# CPU_board.net
KiCad netlist of a schematic drawn in EAGLE
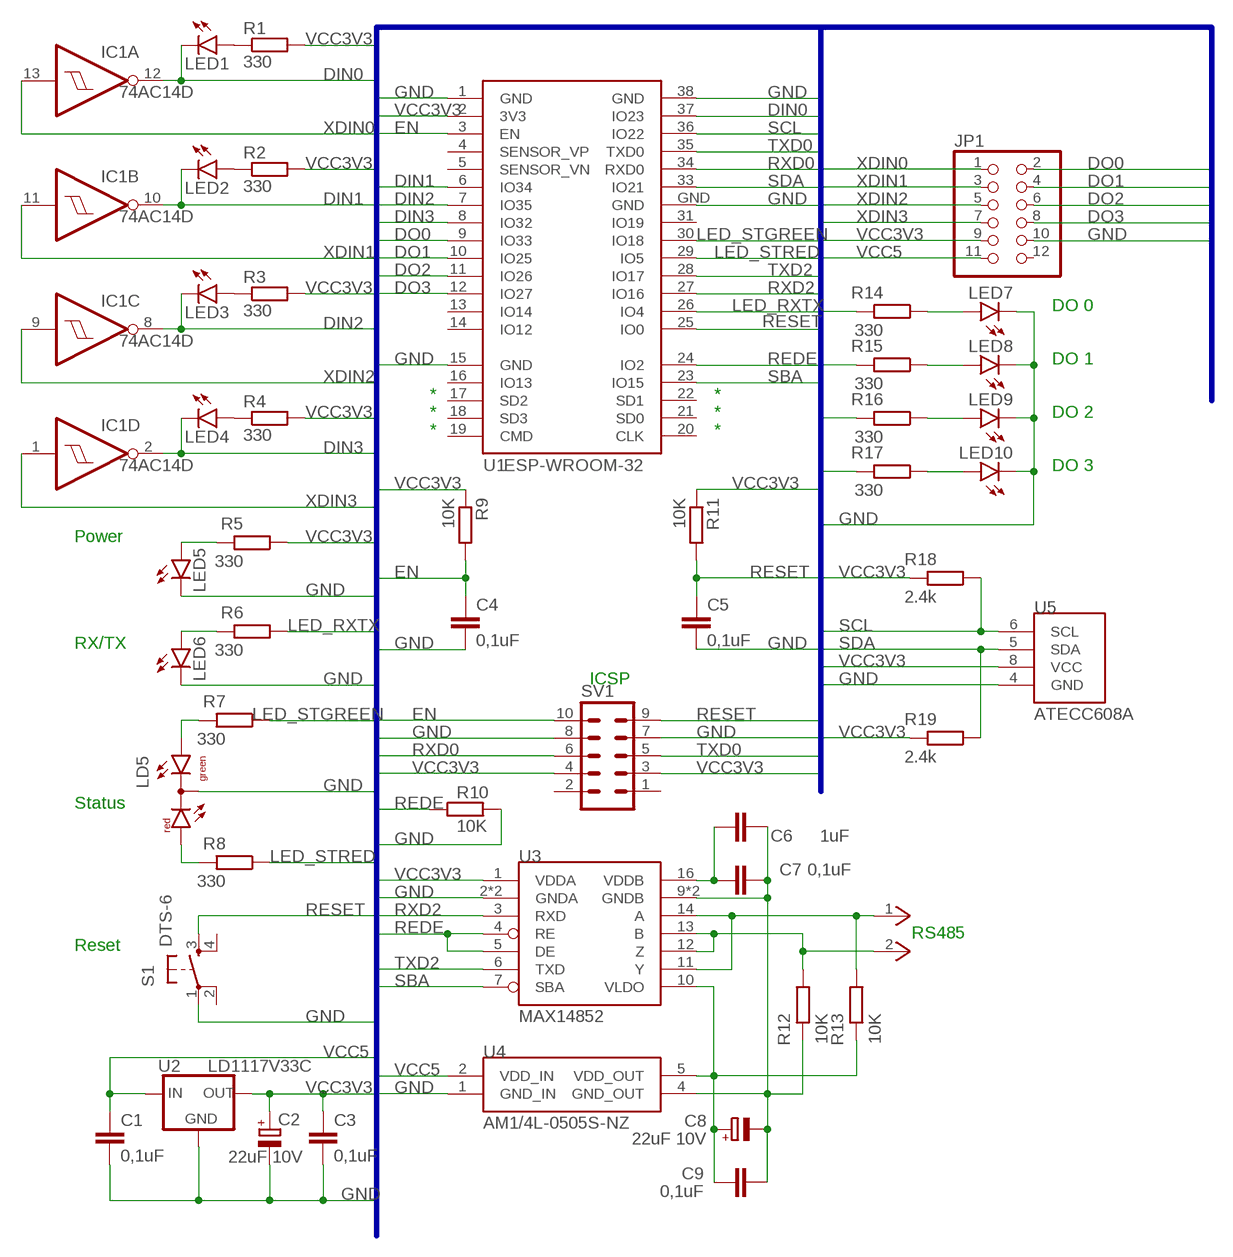
[diagram p0: schematic, sheet 1]

(export (version "E")
  (design (tool "Eeschema 10.0.6"))
  (components
    (comp (ref "C1")
      (value "0,1uF")
      (footprint "eagle-import:C0603")
      (libsource (lib "eagle-import") (part "C-EUC0603"))
    )
    (comp (ref "C2")
      (value "22uF 10V")
      (footprint "eagle-import:PANASONIC_A")
      (libsource (lib "eagle-import") (part "CPOL-EUA"))
    )
    (comp (ref "C3")
      (value "0,1uF")
      (footprint "eagle-import:C0603")
      (libsource (lib "eagle-import") (part "C-EUC0603"))
    )
    (comp (ref "C4")
      (value "0,1uF")
      (footprint "eagle-import:C0603")
      (libsource (lib "eagle-import") (part "C-EUC0603"))
    )
    (comp (ref "C5")
      (value "0,1uF")
      (footprint "eagle-import:C0603")
      (libsource (lib "eagle-import") (part "C-EUC0603"))
    )
    (comp (ref "C6")
      (value "1uF")
      (footprint "eagle-import:C0603")
      (libsource (lib "eagle-import") (part "C-EUC0603"))
    )
    (comp (ref "C7")
      (value "0,1uF")
      (footprint "eagle-import:C0603")
      (libsource (lib "eagle-import") (part "C-EUC0603"))
    )
    (comp (ref "C8")
      (value "22uF 10V")
      (footprint "eagle-import:PANASONIC_D")
      (libsource (lib "eagle-import") (part "CPOL-EUD"))
    )
    (comp (ref "C9")
      (value "0,1uF")
      (footprint "eagle-import:C0603")
      (libsource (lib "eagle-import") (part "C-EUC0603"))
    )
    (comp (ref "IC1")
      (value "74AC14D")
      (footprint "eagle-import:SO14")
      (libsource (lib "eagle-import") (part "7414DAC"))
    )
    (comp (ref "JP1")
      (value "PINHD-2X6")
      (footprint "eagle-import:2X06")
      (libsource (lib "eagle-import") (part "PINHD-2X6"))
    )
    (comp (ref "LD5")
      (value "DUOLED-RG-C")
      (footprint "eagle-import:DUOLED-C-5MM")
      (libsource (lib "eagle-import") (part "DUOLED-RG-C"))
    )
    (comp (ref "LED1")
      (value "LED5MM")
      (footprint "eagle-import:LED5MM")
      (libsource (lib "eagle-import") (part "LED5MM"))
    )
    (comp (ref "LED2")
      (value "LED5MM")
      (footprint "eagle-import:LED5MM")
      (libsource (lib "eagle-import") (part "LED5MM"))
    )
    (comp (ref "LED3")
      (value "LED5MM")
      (footprint "eagle-import:LED5MM")
      (libsource (lib "eagle-import") (part "LED5MM"))
    )
    (comp (ref "LED4")
      (value "LED5MM")
      (footprint "eagle-import:LED5MM")
      (libsource (lib "eagle-import") (part "LED5MM"))
    )
    (comp (ref "LED5")
      (value "LED5MM")
      (footprint "eagle-import:LED5MM")
      (libsource (lib "eagle-import") (part "LED5MM"))
    )
    (comp (ref "LED6")
      (value "LED5MM")
      (footprint "eagle-import:LED5MM")
      (libsource (lib "eagle-import") (part "LED5MM"))
    )
    (comp (ref "LED7")
      (value "LED5MM")
      (footprint "eagle-import:LED5MM")
      (libsource (lib "eagle-import") (part "LED5MM"))
    )
    (comp (ref "LED8")
      (value "LED5MM")
      (footprint "eagle-import:LED5MM")
      (libsource (lib "eagle-import") (part "LED5MM"))
    )
    (comp (ref "LED9")
      (value "LED5MM")
      (footprint "eagle-import:LED5MM")
      (libsource (lib "eagle-import") (part "LED5MM"))
    )
    (comp (ref "LED10")
      (value "LED5MM")
      (footprint "eagle-import:LED5MM")
      (libsource (lib "eagle-import") (part "LED5MM"))
    )
    (comp (ref "R1")
      (value "330")
      (footprint "eagle-import:R0603")
      (libsource (lib "eagle-import") (part "R-EU_R0603"))
    )
    (comp (ref "R2")
      (value "330")
      (footprint "eagle-import:R0603")
      (libsource (lib "eagle-import") (part "R-EU_R0603"))
    )
    (comp (ref "R3")
      (value "330")
      (footprint "eagle-import:R0603")
      (libsource (lib "eagle-import") (part "R-EU_R0603"))
    )
    (comp (ref "R4")
      (value "330")
      (footprint "eagle-import:R0603")
      (libsource (lib "eagle-import") (part "R-EU_R0603"))
    )
    (comp (ref "R5")
      (value "330")
      (footprint "eagle-import:R0603")
      (libsource (lib "eagle-import") (part "R-EU_R0603"))
    )
    (comp (ref "R6")
      (value "330")
      (footprint "eagle-import:R0603")
      (libsource (lib "eagle-import") (part "R-EU_R0603"))
    )
    (comp (ref "R7")
      (value "330")
      (footprint "eagle-import:R0603")
      (libsource (lib "eagle-import") (part "R-EU_R0603"))
    )
    (comp (ref "R8")
      (value "330")
      (footprint "eagle-import:R0603")
      (libsource (lib "eagle-import") (part "R-EU_R0603"))
    )
    (comp (ref "R9")
      (value "10K")
      (footprint "eagle-import:R0603")
      (libsource (lib "eagle-import") (part "R-EU_R0603"))
    )
    (comp (ref "R10")
      (value "10K")
      (footprint "eagle-import:R0603")
      (libsource (lib "eagle-import") (part "R-EU_R0603"))
    )
    (comp (ref "R11")
      (value "10K")
      (footprint "eagle-import:R0603")
      (libsource (lib "eagle-import") (part "R-EU_R0603"))
    )
    (comp (ref "R12")
      (value "10K")
      (footprint "eagle-import:R0603")
      (libsource (lib "eagle-import") (part "R-EU_R0603"))
    )
    (comp (ref "R13")
      (value "10K")
      (footprint "eagle-import:R0603")
      (libsource (lib "eagle-import") (part "R-EU_R0603"))
    )
    (comp (ref "R14")
      (value "330")
      (footprint "eagle-import:R0603")
      (libsource (lib "eagle-import") (part "R-EU_R0603"))
    )
    (comp (ref "R15")
      (value "330")
      (footprint "eagle-import:R0603")
      (libsource (lib "eagle-import") (part "R-EU_R0603"))
    )
    (comp (ref "R16")
      (value "330")
      (footprint "eagle-import:R0603")
      (libsource (lib "eagle-import") (part "R-EU_R0603"))
    )
    (comp (ref "R17")
      (value "330")
      (footprint "eagle-import:R0603")
      (libsource (lib "eagle-import") (part "R-EU_R0603"))
    )
    (comp (ref "R18")
      (value "2.4k")
      (footprint "eagle-import:R0603")
      (libsource (lib "eagle-import") (part "R-EU_R0603"))
    )
    (comp (ref "R19")
      (value "2.4k")
      (footprint "eagle-import:R0603")
      (libsource (lib "eagle-import") (part "R-EU_R0603"))
    )
    (comp (ref "S1")
      (value "DTS-6")
      (footprint "eagle-import:DTS-6")
      (libsource (lib "eagle-import") (part "DTS-6"))
    )
    (comp (ref "SV1")
      (value "ML10")
      (footprint "eagle-import:ML10")
      (libsource (lib "eagle-import") (part "ML10"))
    )
    (comp (ref "U1")
      (value "ESP-WROOM-32")
      (footprint "eagle-import:ESP-WROOM-32")
      (libsource (lib "eagle-import") (part "ESP-WROOM-32"))
    )
    (comp (ref "U2")
      (value "LD1117V33C")
      (footprint "eagle-import:SOT223")
      (libsource (lib "eagle-import") (part "LD1117V33C"))
    )
    (comp (ref "U3")
      (value "MAX14852")
      (footprint "eagle-import:SO16")
      (libsource (lib "eagle-import") (part "MAX14852"))
    )
    (comp (ref "U4")
      (value "AM1/4L-0505S-NZ")
      (footprint "eagle-import:AM1_4L")
      (libsource (lib "eagle-import") (part "AM1/4L"))
    )
    (comp (ref "U5")
      (value "ATECC608A")
      (footprint "eagle-import:SOIC8")
      (libsource (lib "eagle-import") (part "ATECC608A"))
    )
    (comp (ref "X1")
      (value "2EHDCR-5.08-02P")
      (footprint "eagle-import:2EHDCR-5.08-02P")
      (libsource (lib "eagle-import") (part "2EHDCR-5.08-02P"))
    )
  )
  (nets
    (net (code "1") (name "/DIN0") (class "Default")
      (node (ref "IC1") (pin "12") (pinfunction "O_12") (pintype "output"))
      (node (ref "LED1") (pin "K") (pinfunction "C_K") (pintype "passive"))
      (node (ref "U1") (pin "37") (pinfunction "IO23_37") (pintype "bidirectional"))
    )
    (net (code "2") (name "/DIN1") (class "Default")
      (node (ref "IC1") (pin "10") (pinfunction "O_10") (pintype "output"))
      (node (ref "LED2") (pin "K") (pinfunction "C_K") (pintype "passive"))
      (node (ref "U1") (pin "6") (pinfunction "IO34_6") (pintype "bidirectional"))
    )
    (net (code "3") (name "/DIN2") (class "Default")
      (node (ref "IC1") (pin "8") (pinfunction "O_8") (pintype "output"))
      (node (ref "LED3") (pin "K") (pinfunction "C_K") (pintype "passive"))
      (node (ref "U1") (pin "7") (pinfunction "IO35_7") (pintype "bidirectional"))
    )
    (net (code "4") (name "/DIN3") (class "Default")
      (node (ref "IC1") (pin "2") (pinfunction "O_2") (pintype "output"))
      (node (ref "LED4") (pin "K") (pinfunction "C_K") (pintype "passive"))
      (node (ref "U1") (pin "8") (pinfunction "IO32_8") (pintype "bidirectional"))
    )
    (net (code "5") (name "/DO0") (class "Default")
      (node (ref "JP1") (pin "2") (pinfunction "2_2") (pintype "passive"))
      (node (ref "R14") (pin "2") (pinfunction "2_2") (pintype "passive"))
      (node (ref "U1") (pin "9") (pinfunction "IO33_9") (pintype "bidirectional"))
    )
    (net (code "6") (name "/DO1") (class "Default")
      (node (ref "JP1") (pin "4") (pinfunction "4_4") (pintype "passive"))
      (node (ref "R15") (pin "2") (pinfunction "2_2") (pintype "passive"))
      (node (ref "U1") (pin "10") (pinfunction "IO25_10") (pintype "bidirectional"))
    )
    (net (code "7") (name "/DO2") (class "Default")
      (node (ref "JP1") (pin "6") (pinfunction "6_6") (pintype "passive"))
      (node (ref "R16") (pin "2") (pinfunction "2_2") (pintype "passive"))
      (node (ref "U1") (pin "11") (pinfunction "IO26_11") (pintype "bidirectional"))
    )
    (net (code "8") (name "/DO3") (class "Default")
      (node (ref "JP1") (pin "8") (pinfunction "8_8") (pintype "passive"))
      (node (ref "R17") (pin "2") (pinfunction "2_2") (pintype "passive"))
      (node (ref "U1") (pin "12") (pinfunction "IO27_12") (pintype "bidirectional"))
    )
    (net (code "9") (name "/EN") (class "Default")
      (node (ref "C4") (pin "1") (pinfunction "1_1") (pintype "passive"))
      (node (ref "R9") (pin "2") (pinfunction "2_2") (pintype "passive"))
      (node (ref "SV1") (pin "10") (pinfunction "10_10") (pintype "passive"))
      (node (ref "U1") (pin "3") (pinfunction "EN_3") (pintype "input"))
    )
    (net (code "10") (name "/GND") (class "Default")
      (node (ref "C1") (pin "2") (pinfunction "2_2") (pintype "passive"))
      (node (ref "C2") (pin "-") (pinfunction "-_-") (pintype "passive"))
      (node (ref "C3") (pin "2") (pinfunction "2_2") (pintype "passive"))
      (node (ref "C4") (pin "2") (pinfunction "2_2") (pintype "passive"))
      (node (ref "C5") (pin "2") (pinfunction "2_2") (pintype "passive"))
      (node (ref "JP1") (pin "10") (pinfunction "10_10") (pintype "passive"))
      (node (ref "LD5") (pin "C") (pinfunction "C_C") (pintype "passive"))
      (node (ref "LED10") (pin "K") (pinfunction "C_K") (pintype "passive"))
      (node (ref "LED5") (pin "K") (pinfunction "C_K") (pintype "passive"))
      (node (ref "LED6") (pin "K") (pinfunction "C_K") (pintype "passive"))
      (node (ref "LED7") (pin "K") (pinfunction "C_K") (pintype "passive"))
      (node (ref "LED8") (pin "K") (pinfunction "C_K") (pintype "passive"))
      (node (ref "LED9") (pin "K") (pinfunction "C_K") (pintype "passive"))
      (node (ref "R10") (pin "2") (pinfunction "2_2") (pintype "passive"))
      (node (ref "S1") (pin "1") (pinfunction "1_1") (pintype "passive"))
      (node (ref "SV1") (pin "7") (pinfunction "7_7") (pintype "passive"))
      (node (ref "SV1") (pin "8") (pinfunction "8_8") (pintype "passive"))
      (node (ref "U1") (pin "1") (pinfunction "GND_1") (pintype "power_in"))
      (node (ref "U1") (pin "15") (pinfunction "GND_15") (pintype "power_in"))
      (node (ref "U1") (pin "38") (pinfunction "GND_38") (pintype "power_in"))
      (node (ref "U1") (pin "GND") (pinfunction "GND_GND") (pintype "power_in"))
      (node (ref "U2") (pin "1") (pinfunction "GND_1") (pintype "input"))
      (node (ref "U3") (pin "2") (pinfunction "GNDA_2") (pintype "bidirectional"))
      (node (ref "U3") (pin "8") (pinfunction "GNDA_8") (pintype "bidirectional"))
      (node (ref "U4") (pin "1") (pinfunction "GND_IN_1") (pintype "bidirectional"))
      (node (ref "U5") (pin "4") (pinfunction "GND_4") (pintype "bidirectional"))
    )
    (net (code "11") (name "/LED_RXTX") (class "Default")
      (node (ref "R6") (pin "1") (pinfunction "1_1") (pintype "passive"))
      (node (ref "U1") (pin "26") (pinfunction "IO4_26") (pintype "bidirectional"))
    )
    (net (code "12") (name "/LED_STGREEN") (class "Default")
      (node (ref "R7") (pin "1") (pinfunction "1_1") (pintype "passive"))
      (node (ref "U1") (pin "30") (pinfunction "IO18_30") (pintype "bidirectional"))
    )
    (net (code "13") (name "/LED_STRED") (class "Default")
      (node (ref "R8") (pin "1") (pinfunction "1_1") (pintype "passive"))
      (node (ref "U1") (pin "29") (pinfunction "IO5_29") (pintype "bidirectional"))
    )
    (net (code "14") (name "/REDE") (class "Default")
      (node (ref "R10") (pin "1") (pinfunction "1_1") (pintype "passive"))
      (node (ref "U1") (pin "24") (pinfunction "IO2_24") (pintype "bidirectional"))
      (node (ref "U3") (pin "4") (pinfunction "RE_4") (pintype "bidirectional"))
      (node (ref "U3") (pin "5") (pinfunction "DE_5") (pintype "bidirectional"))
    )
    (net (code "15") (name "/RESET") (class "Default")
      (node (ref "C5") (pin "1") (pinfunction "1_1") (pintype "passive"))
      (node (ref "R11") (pin "2") (pinfunction "2_2") (pintype "passive"))
      (node (ref "S1") (pin "3") (pinfunction "3_3") (pintype "passive"))
      (node (ref "SV1") (pin "9") (pinfunction "9_9") (pintype "passive"))
      (node (ref "U1") (pin "25") (pinfunction "IO0_25") (pintype "bidirectional"))
    )
    (net (code "16") (name "/RXD0") (class "Default")
      (node (ref "SV1") (pin "6") (pinfunction "6_6") (pintype "passive"))
      (node (ref "U1") (pin "34") (pinfunction "RXD0_34") (pintype "bidirectional"))
    )
    (net (code "17") (name "/RXD2") (class "Default")
      (node (ref "U1") (pin "27") (pinfunction "IO16_27") (pintype "bidirectional"))
      (node (ref "U3") (pin "3") (pinfunction "RXD_3") (pintype "bidirectional"))
    )
    (net (code "18") (name "/SBA") (class "Default")
      (node (ref "U1") (pin "23") (pinfunction "IO15_23") (pintype "bidirectional"))
      (node (ref "U3") (pin "7") (pinfunction "SBA_7") (pintype "bidirectional"))
    )
    (net (code "19") (name "/SCL") (class "Default")
      (node (ref "R18") (pin "1") (pinfunction "1_1") (pintype "passive"))
      (node (ref "U1") (pin "36") (pinfunction "IO22_36") (pintype "bidirectional"))
      (node (ref "U5") (pin "6") (pinfunction "SCL_6") (pintype "bidirectional"))
    )
    (net (code "20") (name "/SDA") (class "Default")
      (node (ref "R19") (pin "1") (pinfunction "1_1") (pintype "passive"))
      (node (ref "U1") (pin "33") (pinfunction "IO21_33") (pintype "bidirectional"))
      (node (ref "U5") (pin "5") (pinfunction "SDA_5") (pintype "bidirectional"))
    )
    (net (code "21") (name "/TXD0") (class "Default")
      (node (ref "SV1") (pin "5") (pinfunction "5_5") (pintype "passive"))
      (node (ref "U1") (pin "35") (pinfunction "TXD0_35") (pintype "bidirectional"))
    )
    (net (code "22") (name "/TXD2") (class "Default")
      (node (ref "U1") (pin "28") (pinfunction "IO17_28") (pintype "bidirectional"))
      (node (ref "U3") (pin "6") (pinfunction "TXD_6") (pintype "bidirectional"))
    )
    (net (code "23") (name "/VCC3V3") (class "Default")
      (node (ref "C2") (pin "+") (pinfunction "+_+") (pintype "passive"))
      (node (ref "C3") (pin "1") (pinfunction "1_1") (pintype "passive"))
      (node (ref "JP1") (pin "9") (pinfunction "9_9") (pintype "passive"))
      (node (ref "R1") (pin "2") (pinfunction "2_2") (pintype "passive"))
      (node (ref "R11") (pin "1") (pinfunction "1_1") (pintype "passive"))
      (node (ref "R18") (pin "2") (pinfunction "2_2") (pintype "passive"))
      (node (ref "R19") (pin "2") (pinfunction "2_2") (pintype "passive"))
      (node (ref "R2") (pin "2") (pinfunction "2_2") (pintype "passive"))
      (node (ref "R3") (pin "2") (pinfunction "2_2") (pintype "passive"))
      (node (ref "R4") (pin "2") (pinfunction "2_2") (pintype "passive"))
      (node (ref "R5") (pin "1") (pinfunction "1_1") (pintype "passive"))
      (node (ref "R9") (pin "1") (pinfunction "1_1") (pintype "passive"))
      (node (ref "SV1") (pin "3") (pinfunction "3_3") (pintype "passive"))
      (node (ref "SV1") (pin "4") (pinfunction "4_4") (pintype "passive"))
      (node (ref "U1") (pin "2") (pinfunction "3V3_2") (pintype "power_in"))
      (node (ref "U2") (pin "2") (pinfunction "OUT_2") (pintype "output"))
      (node (ref "U2") (pin "4") (pinfunction "OUT_4") (pintype "output"))
      (node (ref "U3") (pin "1") (pinfunction "VDDA_1") (pintype "bidirectional"))
      (node (ref "U5") (pin "8") (pinfunction "VCC_8") (pintype "bidirectional"))
    )
    (net (code "24") (name "/VCC5") (class "Default")
      (node (ref "C1") (pin "1") (pinfunction "1_1") (pintype "passive"))
      (node (ref "JP1") (pin "11") (pinfunction "11_11") (pintype "passive"))
      (node (ref "U2") (pin "3") (pinfunction "IN_3") (pintype "input"))
      (node (ref "U4") (pin "2") (pinfunction "VDD_IN_2") (pintype "bidirectional"))
    )
    (net (code "25") (name "/XDIN0") (class "Default")
      (node (ref "IC1") (pin "13") (pinfunction "I_13") (pintype "input"))
      (node (ref "JP1") (pin "1") (pinfunction "1_1") (pintype "passive"))
    )
    (net (code "26") (name "/XDIN1") (class "Default")
      (node (ref "IC1") (pin "11") (pinfunction "I_11") (pintype "input"))
      (node (ref "JP1") (pin "3") (pinfunction "3_3") (pintype "passive"))
    )
    (net (code "27") (name "/XDIN2") (class "Default")
      (node (ref "IC1") (pin "9") (pinfunction "I_9") (pintype "input"))
      (node (ref "JP1") (pin "5") (pinfunction "5_5") (pintype "passive"))
    )
    (net (code "28") (name "/XDIN3") (class "Default")
      (node (ref "IC1") (pin "1") (pinfunction "I_1") (pintype "input"))
      (node (ref "JP1") (pin "7") (pinfunction "7_7") (pintype "passive"))
    )
    (net (code "29") (name "Net-(LD5-AG)") (class "Default")
      (node (ref "LD5") (pin "AX") (pinfunction "AG_AX") (pintype "passive"))
      (node (ref "R7") (pin "2") (pinfunction "2_2") (pintype "passive"))
    )
    (net (code "30") (name "Net-(LD5-PadAR)") (class "Default")
      (node (ref "LD5") (pin "AR") (pinfunction "AR_AR") (pintype "passive"))
      (node (ref "R8") (pin "2") (pinfunction "2_2") (pintype "passive"))
    )
    (net (code "31") (name "Net-(LED1-PadA)") (class "Default")
      (node (ref "LED1") (pin "A") (pinfunction "A_A") (pintype "passive"))
      (node (ref "R1") (pin "1") (pinfunction "1_1") (pintype "passive"))
    )
    (net (code "32") (name "Net-(LED2-PadA)") (class "Default")
      (node (ref "LED2") (pin "A") (pinfunction "A_A") (pintype "passive"))
      (node (ref "R2") (pin "1") (pinfunction "1_1") (pintype "passive"))
    )
    (net (code "33") (name "Net-(LED3-PadA)") (class "Default")
      (node (ref "LED3") (pin "A") (pinfunction "A_A") (pintype "passive"))
      (node (ref "R3") (pin "1") (pinfunction "1_1") (pintype "passive"))
    )
    (net (code "34") (name "Net-(LED4-PadA)") (class "Default")
      (node (ref "LED4") (pin "A") (pinfunction "A_A") (pintype "passive"))
      (node (ref "R4") (pin "1") (pinfunction "1_1") (pintype "passive"))
    )
    (net (code "35") (name "Net-(LED5-PadA)") (class "Default")
      (node (ref "LED5") (pin "A") (pinfunction "A_A") (pintype "passive"))
      (node (ref "R5") (pin "2") (pinfunction "2_2") (pintype "passive"))
    )
    (net (code "36") (name "Net-(LED6-PadA)") (class "Default")
      (node (ref "LED6") (pin "A") (pinfunction "A_A") (pintype "passive"))
      (node (ref "R6") (pin "2") (pinfunction "2_2") (pintype "passive"))
    )
    (net (code "37") (name "Net-(LED7-PadA)") (class "Default")
      (node (ref "LED7") (pin "A") (pinfunction "A_A") (pintype "passive"))
      (node (ref "R14") (pin "1") (pinfunction "1_1") (pintype "passive"))
    )
    (net (code "38") (name "Net-(LED8-PadA)") (class "Default")
      (node (ref "LED8") (pin "A") (pinfunction "A_A") (pintype "passive"))
      (node (ref "R15") (pin "1") (pinfunction "1_1") (pintype "passive"))
    )
    (net (code "39") (name "Net-(LED9-PadA)") (class "Default")
      (node (ref "LED9") (pin "A") (pinfunction "A_A") (pintype "passive"))
      (node (ref "R16") (pin "1") (pinfunction "1_1") (pintype "passive"))
    )
    (net (code "40") (name "Net-(LED10-PadA)") (class "Default")
      (node (ref "LED10") (pin "A") (pinfunction "A_A") (pintype "passive"))
      (node (ref "R17") (pin "1") (pinfunction "1_1") (pintype "passive"))
    )
    (net (code "41") (name "Net-(U3-A)") (class "Default")
      (node (ref "R13") (pin "1") (pinfunction "1_1") (pintype "passive"))
      (node (ref "U3") (pin "11") (pinfunction "Y_11") (pintype "bidirectional"))
      (node (ref "U3") (pin "14") (pinfunction "A_14") (pintype "bidirectional"))
      (node (ref "X1") (pin "1") (pinfunction "1_1") (pintype "passive"))
    )
    (net (code "42") (name "Net-(U3-B)") (class "Default")
      (node (ref "R12") (pin "1") (pinfunction "1_1") (pintype "passive"))
      (node (ref "U3") (pin "12") (pinfunction "Z_12") (pintype "bidirectional"))
      (node (ref "U3") (pin "13") (pinfunction "B_13") (pintype "bidirectional"))
      (node (ref "X1") (pin "2") (pinfunction "1_2") (pintype "passive"))
    )
    (net (code "43") (name "Net-(U3-VDDB)") (class "Default")
      (node (ref "C6") (pin "1") (pinfunction "1_1") (pintype "passive"))
      (node (ref "C7") (pin "1") (pinfunction "1_1") (pintype "passive"))
      (node (ref "U3") (pin "16") (pinfunction "VDDB_16") (pintype "bidirectional"))
    )
    (net (code "44") (name "Net-(U3-VLDO)") (class "Default")
      (node (ref "C8") (pin "+") (pinfunction "+_+") (pintype "passive"))
      (node (ref "C9") (pin "1") (pinfunction "1_1") (pintype "passive"))
      (node (ref "R13") (pin "2") (pinfunction "2_2") (pintype "passive"))
      (node (ref "U3") (pin "10") (pinfunction "VLDO_10") (pintype "bidirectional"))
      (node (ref "U4") (pin "5") (pinfunction "VDD_OUT_5") (pintype "bidirectional"))
    )
    (net (code "45") (name "Net-(U4-GND_OUT)") (class "Default")
      (node (ref "C6") (pin "2") (pinfunction "2_2") (pintype "passive"))
      (node (ref "C7") (pin "2") (pinfunction "2_2") (pintype "passive"))
      (node (ref "C8") (pin "-") (pinfunction "-_-") (pintype "passive"))
      (node (ref "C9") (pin "2") (pinfunction "2_2") (pintype "passive"))
      (node (ref "R12") (pin "2") (pinfunction "2_2") (pintype "passive"))
      (node (ref "U3") (pin "15") (pinfunction "GNDB_15") (pintype "bidirectional"))
      (node (ref "U3") (pin "9") (pinfunction "GNDB_9") (pintype "bidirectional"))
      (node (ref "U4") (pin "4") (pinfunction "GND_OUT_4") (pintype "bidirectional"))
    )
    (net (code "46") (name "unconnected-(JP1-Pad12)") (class "Default")
      (node (ref "JP1") (pin "12") (pinfunction "12_12") (pintype "passive"))
    )
    (net (code "47") (name "unconnected-(S1-Pad2)") (class "Default")
      (node (ref "S1") (pin "2") (pinfunction "2_2") (pintype "passive"))
    )
    (net (code "48") (name "unconnected-(S1-Pad4)") (class "Default")
      (node (ref "S1") (pin "4") (pinfunction "4_4") (pintype "passive"))
    )
    (net (code "49") (name "unconnected-(SV1-Pad1)") (class "Default")
      (node (ref "SV1") (pin "1") (pinfunction "1_1") (pintype "passive"))
    )
    (net (code "50") (name "unconnected-(SV1-Pad2)") (class "Default")
      (node (ref "SV1") (pin "2") (pinfunction "2_2") (pintype "passive"))
    )
    (net (code "51") (name "unconnected-(U1-CLK-Pad20)") (class "Default")
      (node (ref "U1") (pin "20") (pinfunction "CLK_20") (pintype "bidirectional"))
    )
    (net (code "52") (name "unconnected-(U1-CMD-Pad19)") (class "Default")
      (node (ref "U1") (pin "19") (pinfunction "CMD_19") (pintype "bidirectional"))
    )
    (net (code "53") (name "unconnected-(U1-IO12-Pad14)") (class "Default")
      (node (ref "U1") (pin "14") (pinfunction "IO12_14") (pintype "bidirectional"))
    )
    (net (code "54") (name "unconnected-(U1-IO13-Pad16)") (class "Default")
      (node (ref "U1") (pin "16") (pinfunction "IO13_16") (pintype "bidirectional"))
    )
    (net (code "55") (name "unconnected-(U1-IO14-Pad13)") (class "Default")
      (node (ref "U1") (pin "13") (pinfunction "IO14_13") (pintype "bidirectional"))
    )
    (net (code "56") (name "unconnected-(U1-IO19-Pad31)") (class "Default")
      (node (ref "U1") (pin "31") (pinfunction "IO19_31") (pintype "bidirectional"))
    )
    (net (code "57") (name "unconnected-(U1-SD0-Pad21)") (class "Default")
      (node (ref "U1") (pin "21") (pinfunction "SD0_21") (pintype "bidirectional"))
    )
    (net (code "58") (name "unconnected-(U1-SD1-Pad22)") (class "Default")
      (node (ref "U1") (pin "22") (pinfunction "SD1_22") (pintype "bidirectional"))
    )
    (net (code "59") (name "unconnected-(U1-SD2-Pad17)") (class "Default")
      (node (ref "U1") (pin "17") (pinfunction "SD2_17") (pintype "bidirectional"))
    )
    (net (code "60") (name "unconnected-(U1-SD3-Pad18)") (class "Default")
      (node (ref "U1") (pin "18") (pinfunction "SD3_18") (pintype "bidirectional"))
    )
    (net (code "61") (name "unconnected-(U1-SENSOR_VN-Pad5)") (class "Default")
      (node (ref "U1") (pin "5") (pinfunction "SENSOR_VN_5") (pintype "bidirectional"))
    )
    (net (code "62") (name "unconnected-(U1-SENSOR_VP-Pad4)") (class "Default")
      (node (ref "U1") (pin "4") (pinfunction "SENSOR_VP_4") (pintype "bidirectional"))
    )
  )
)
